# led-cc-driver-mk-1.net
KiCad netlist of a schematic drawn in EAGLE
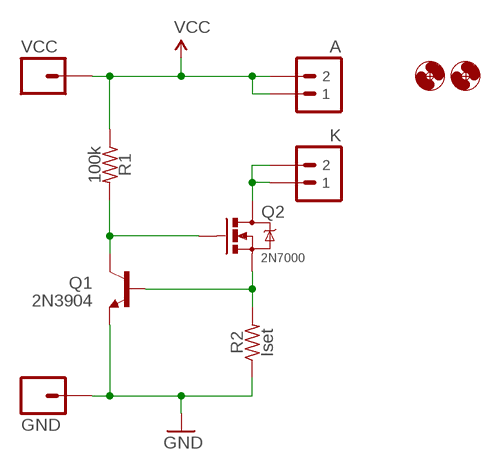
[diagram p0: schematic, sheet 1]

(export (version "E")
  (design (tool "Eeschema 10.0.6"))
  (components
    (comp (ref "A")
      (value "M02PTH")
      (footprint "eagle-import:1X02")
      (libsource (lib "eagle-import") (part "M02PTH"))
    )
    (comp (ref "GND")
      (value "M01PTH")
      (footprint "eagle-import:1X01")
      (libsource (lib "eagle-import") (part "M01PTH"))
    )
    (comp (ref "H1")
      (value "HOLE#2")
      (footprint "eagle-import:HOLE-#2")
      (libsource (lib "eagle-import") (part "HOLE#2"))
    )
    (comp (ref "H2")
      (value "HOLE#2")
      (footprint "eagle-import:HOLE-#2")
      (libsource (lib "eagle-import") (part "HOLE#2"))
    )
    (comp (ref "K")
      (value "M02PTH")
      (footprint "eagle-import:1X02")
      (libsource (lib "eagle-import") (part "M02PTH"))
    )
    (comp (ref "Q1")
      (value "2N3904")
      (footprint "eagle-import:TO-92-AMMO")
      (libsource (lib "eagle-import") (part "TRANSISTOR_NPNTO-92-AMMO-EBC"))
    )
    (comp (ref "Q2")
      (value "2N7000")
      (footprint "eagle-import:TO-92-AMMO")
      (libsource (lib "eagle-import") (part "MOSFET-NCHANNEL2N7000-AMMO"))
    )
    (comp (ref "R1")
      (value "100k")
      (footprint "eagle-import:RESISTOR-AXIAL-PTH-7.62MM")
      (libsource (lib "eagle-import") (part "RESISTORPTH-AXIAL-7.62MM"))
    )
    (comp (ref "R2")
      (value "Iset")
      (footprint "eagle-import:RESISTOR-AXIAL-PTH-7.62MM")
      (libsource (lib "eagle-import") (part "RESISTORPTH-AXIAL-7.62MM"))
    )
    (comp (ref "VCC")
      (value "M01PTH")
      (footprint "eagle-import:1X01")
      (libsource (lib "eagle-import") (part "M01PTH"))
    )
  )
  (nets
    (net (code "1") (name "GND") (class "Default")
      (node (ref "GND") (pin "1") (pinfunction "1_1") (pintype "passive"))
      (node (ref "Q1") (pin "1") (pinfunction "E_1") (pintype "passive"))
      (node (ref "R2") (pin "P$1") (pinfunction "1_P$1") (pintype "passive"))
    )
    (net (code "2") (name "Net-(Q1-B)") (class "Default")
      (node (ref "Q1") (pin "2") (pinfunction "B_2") (pintype "passive"))
      (node (ref "Q2") (pin "1") (pinfunction "S_1") (pintype "passive"))
      (node (ref "R2") (pin "P$2") (pinfunction "2_P$2") (pintype "passive"))
    )
    (net (code "3") (name "Net-(Q1-C)") (class "Default")
      (node (ref "Q1") (pin "3") (pinfunction "C_3") (pintype "passive"))
      (node (ref "Q2") (pin "2") (pinfunction "G_2") (pintype "passive"))
      (node (ref "R1") (pin "P$2") (pinfunction "2_P$2") (pintype "passive"))
    )
    (net (code "4") (name "Net-(Q2-D)") (class "Default")
      (node (ref "K") (pin "1") (pinfunction "1_1") (pintype "passive"))
      (node (ref "K") (pin "2") (pinfunction "2_2") (pintype "passive"))
      (node (ref "Q2") (pin "3") (pinfunction "D_3") (pintype "passive"))
    )
    (net (code "5") (name "VCC") (class "Default")
      (node (ref "A") (pin "1") (pinfunction "1_1") (pintype "passive"))
      (node (ref "A") (pin "2") (pinfunction "2_2") (pintype "passive"))
      (node (ref "R1") (pin "P$1") (pinfunction "1_P$1") (pintype "passive"))
      (node (ref "VCC") (pin "1") (pinfunction "1_1") (pintype "passive"))
    )
  )
)
